# SLIDER_PB.net
KiCad netlist of a schematic drawn in Altium Designer
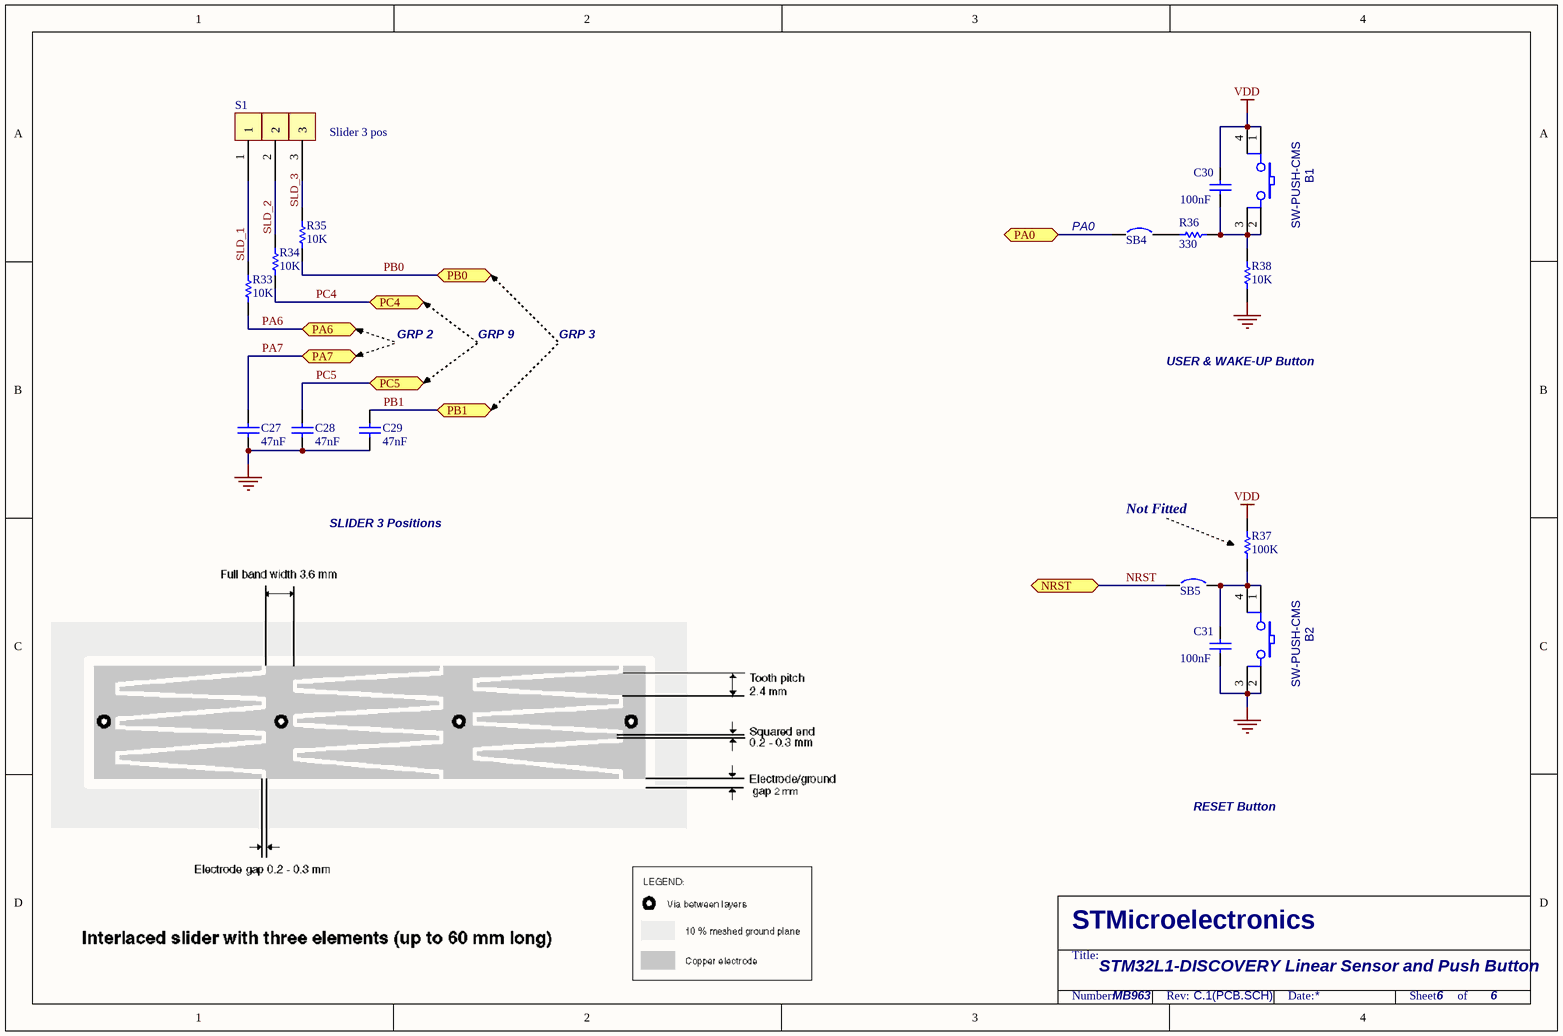
[diagram p0: SLIDER_PB.SchDoc]

(export (version "E")
  (design (tool "Eeschema 10.0.6"))
  (components
    (comp (ref "B1")
      (value "SW-PUSH-CMS")
      (footprint "BP1CMS")
      (description "Non-Open Push-Button 0.1A 24V")
      (libsource (lib "MB913_1") (part "SW-PUSH-CMS"))
    )
    (comp (ref "B2")
      (value "SW-PUSH-CMS")
      (footprint "BP1CMS")
      (description "Non-Open Push-Button 0.1A 24V")
      (libsource (lib "MB913_1") (part "SW-PUSH-CMS"))
    )
    (comp (ref "C27")
      (value "47nF")
      (footprint "0805C")
      (description "Capacitor")
      (fields (field (name "PUBLISHER") "Altium Limited"))
      (libsource (lib "Miscellaneous Devices") (part "CAP"))
    )
    (comp (ref "C28")
      (value "47nF")
      (footprint "0805C")
      (description "Capacitor")
      (fields (field (name "PUBLISHER") "Altium Limited"))
      (libsource (lib "Miscellaneous Devices") (part "CAP"))
    )
    (comp (ref "C29")
      (value "47nF")
      (footprint "0805C")
      (description "Capacitor")
      (fields (field (name "PUBLISHER") "Altium Limited"))
      (libsource (lib "Miscellaneous Devices") (part "CAP"))
    )
    (comp (ref "C30")
      (value "100nF")
      (footprint "0603C")
      (description "Capacitor")
      (fields (field (name "PUBLISHER") "Altium Limited"))
      (libsource (lib "Miscellaneous Devices") (part "CAP"))
    )
    (comp (ref "C31")
      (value "100nF")
      (footprint "0603C")
      (description "Capacitor")
      (fields (field (name "PUBLISHER") "Altium Limited"))
      (libsource (lib "Miscellaneous Devices") (part "CAP"))
    )
    (comp (ref "R33")
      (value "10K")
      (footprint "0402R")
      (description "Resistor")
      (fields (field (name "PUBLISHER") "Altium Limited"))
      (libsource (lib "Miscellaneous Devices") (part "res1"))
    )
    (comp (ref "R34")
      (value "10K")
      (footprint "0402R")
      (description "Resistor")
      (fields (field (name "PUBLISHER") "Altium Limited"))
      (libsource (lib "Miscellaneous Devices") (part "res1"))
    )
    (comp (ref "R35")
      (value "10K")
      (footprint "0402R")
      (description "Resistor")
      (fields (field (name "PUBLISHER") "Altium Limited"))
      (libsource (lib "Miscellaneous Devices") (part "res1"))
    )
    (comp (ref "R36")
      (value "330")
      (footprint "0402R")
      (description "Resistor")
      (fields (field (name "PUBLISHER") "Altium Limited"))
      (libsource (lib "Miscellaneous Devices") (part "res1"))
    )
    (comp (ref "R37")
      (value "100K")
      (footprint "0402R")
      (description "Resistor")
      (fields (field (name "PUBLISHER") "Altium Limited"))
      (libsource (lib "Miscellaneous Devices") (part "res1"))
    )
    (comp (ref "R38")
      (value "10K")
      (footprint "0402R")
      (description "Resistor")
      (fields (field (name "PUBLISHER") "Altium Limited"))
      (libsource (lib "Miscellaneous Devices") (part "res1"))
    )
    (comp (ref "S1")
      (value "Slider 3 pos")
      (footprint "Slider 3-2")
      (description "plan de cuivre recouvert de vernis")
      (libsource (lib "MB963_1") (part "Slider 3 pos"))
    )
    (comp (ref "SB4")
      (value "Circuit Breaker")
      (footprint "JP2_SMD")
      (fields (field (name "PUBLISHER") "Altium Limited"))
      (libsource (lib "MB915") (part "Circuit Breaker"))
    )
    (comp (ref "SB5")
      (value "Circuit Breaker")
      (footprint "JP2_SMD")
      (fields (field (name "PUBLISHER") "Altium Limited"))
      (libsource (lib "MB915") (part "Circuit Breaker"))
    )
  )
  (nets
    (net (code "1") (name "/NRST") (class "Default")
      (node (ref "SB5") (pin "1") (pinfunction "1_1") (pintype "passive"))
    )
    (net (code "2") (name "/PA0") (class "Default")
      (node (ref "SB4") (pin "1") (pinfunction "1_1") (pintype "passive"))
    )
    (net (code "3") (name "/PA6") (class "Default")
      (node (ref "R33") (pin "1") (pinfunction "1_1") (pintype "passive"))
    )
    (net (code "4") (name "/PA7") (class "Default")
      (node (ref "C27") (pin "2") (pinfunction "2_2") (pintype "passive"))
    )
    (net (code "5") (name "/PB0") (class "Default")
      (node (ref "R35") (pin "1") (pinfunction "1_1") (pintype "passive"))
    )
    (net (code "6") (name "/PB1") (class "Default")
      (node (ref "C29") (pin "2") (pinfunction "2_2") (pintype "passive"))
    )
    (net (code "7") (name "/PC4") (class "Default")
      (node (ref "R34") (pin "1") (pinfunction "1_1") (pintype "passive"))
    )
    (net (code "8") (name "/PC5") (class "Default")
      (node (ref "C28") (pin "2") (pinfunction "2_2") (pintype "passive"))
    )
    (net (code "9") (name "/SLD_1") (class "Default")
      (node (ref "R33") (pin "2") (pinfunction "2_2") (pintype "passive"))
      (node (ref "S1") (pin "1") (pinfunction "1_1") (pintype "passive"))
    )
    (net (code "10") (name "/SLD_2") (class "Default")
      (node (ref "R34") (pin "2") (pinfunction "2_2") (pintype "passive"))
      (node (ref "S1") (pin "2") (pinfunction "2_2") (pintype "passive"))
    )
    (net (code "11") (name "/SLD_3") (class "Default")
      (node (ref "R35") (pin "2") (pinfunction "2_2") (pintype "passive"))
      (node (ref "S1") (pin "3") (pinfunction "3_3") (pintype "passive"))
    )
    (net (code "12") (name "GND") (class "Default")
      (node (ref "B2") (pin "2") (pinfunction "2_2") (pintype "passive"))
      (node (ref "B2") (pin "3") (pinfunction "3_3") (pintype "passive"))
      (node (ref "C27") (pin "1") (pinfunction "1_1") (pintype "passive"))
      (node (ref "C28") (pin "1") (pinfunction "1_1") (pintype "passive"))
      (node (ref "C29") (pin "1") (pinfunction "1_1") (pintype "passive"))
      (node (ref "C31") (pin "1") (pinfunction "1_1") (pintype "passive"))
      (node (ref "R38") (pin "1") (pinfunction "1_1") (pintype "passive"))
    )
    (net (code "13") (name "Net-(B1-Pad2)") (class "Default")
      (node (ref "B1") (pin "2") (pinfunction "2_2") (pintype "passive"))
      (node (ref "B1") (pin "3") (pinfunction "3_3") (pintype "passive"))
      (node (ref "C30") (pin "1") (pinfunction "1_1") (pintype "passive"))
      (node (ref "R36") (pin "2") (pinfunction "2_2") (pintype "passive"))
      (node (ref "R38") (pin "2") (pinfunction "2_2") (pintype "passive"))
    )
    (net (code "14") (name "Net-(B2-Pad1)") (class "Default")
      (node (ref "B2") (pin "1") (pinfunction "1_1") (pintype "passive"))
      (node (ref "B2") (pin "4") (pinfunction "4_4") (pintype "passive"))
      (node (ref "C31") (pin "2") (pinfunction "2_2") (pintype "passive"))
      (node (ref "R37") (pin "1") (pinfunction "1_1") (pintype "passive"))
      (node (ref "SB5") (pin "2") (pinfunction "2_2") (pintype "passive"))
    )
    (net (code "15") (name "Net-(R36-Pad1)") (class "Default")
      (node (ref "R36") (pin "1") (pinfunction "1_1") (pintype "passive"))
      (node (ref "SB4") (pin "2") (pinfunction "2_2") (pintype "passive"))
    )
    (net (code "16") (name "VDD") (class "Default")
      (node (ref "B1") (pin "1") (pinfunction "1_1") (pintype "passive"))
      (node (ref "B1") (pin "4") (pinfunction "4_4") (pintype "passive"))
      (node (ref "C30") (pin "2") (pinfunction "2_2") (pintype "passive"))
      (node (ref "R37") (pin "2") (pinfunction "2_2") (pintype "passive"))
    )
  )
)
